# Voxx_Dott.net
KiCad netlist of a schematic drawn in EasyEDA
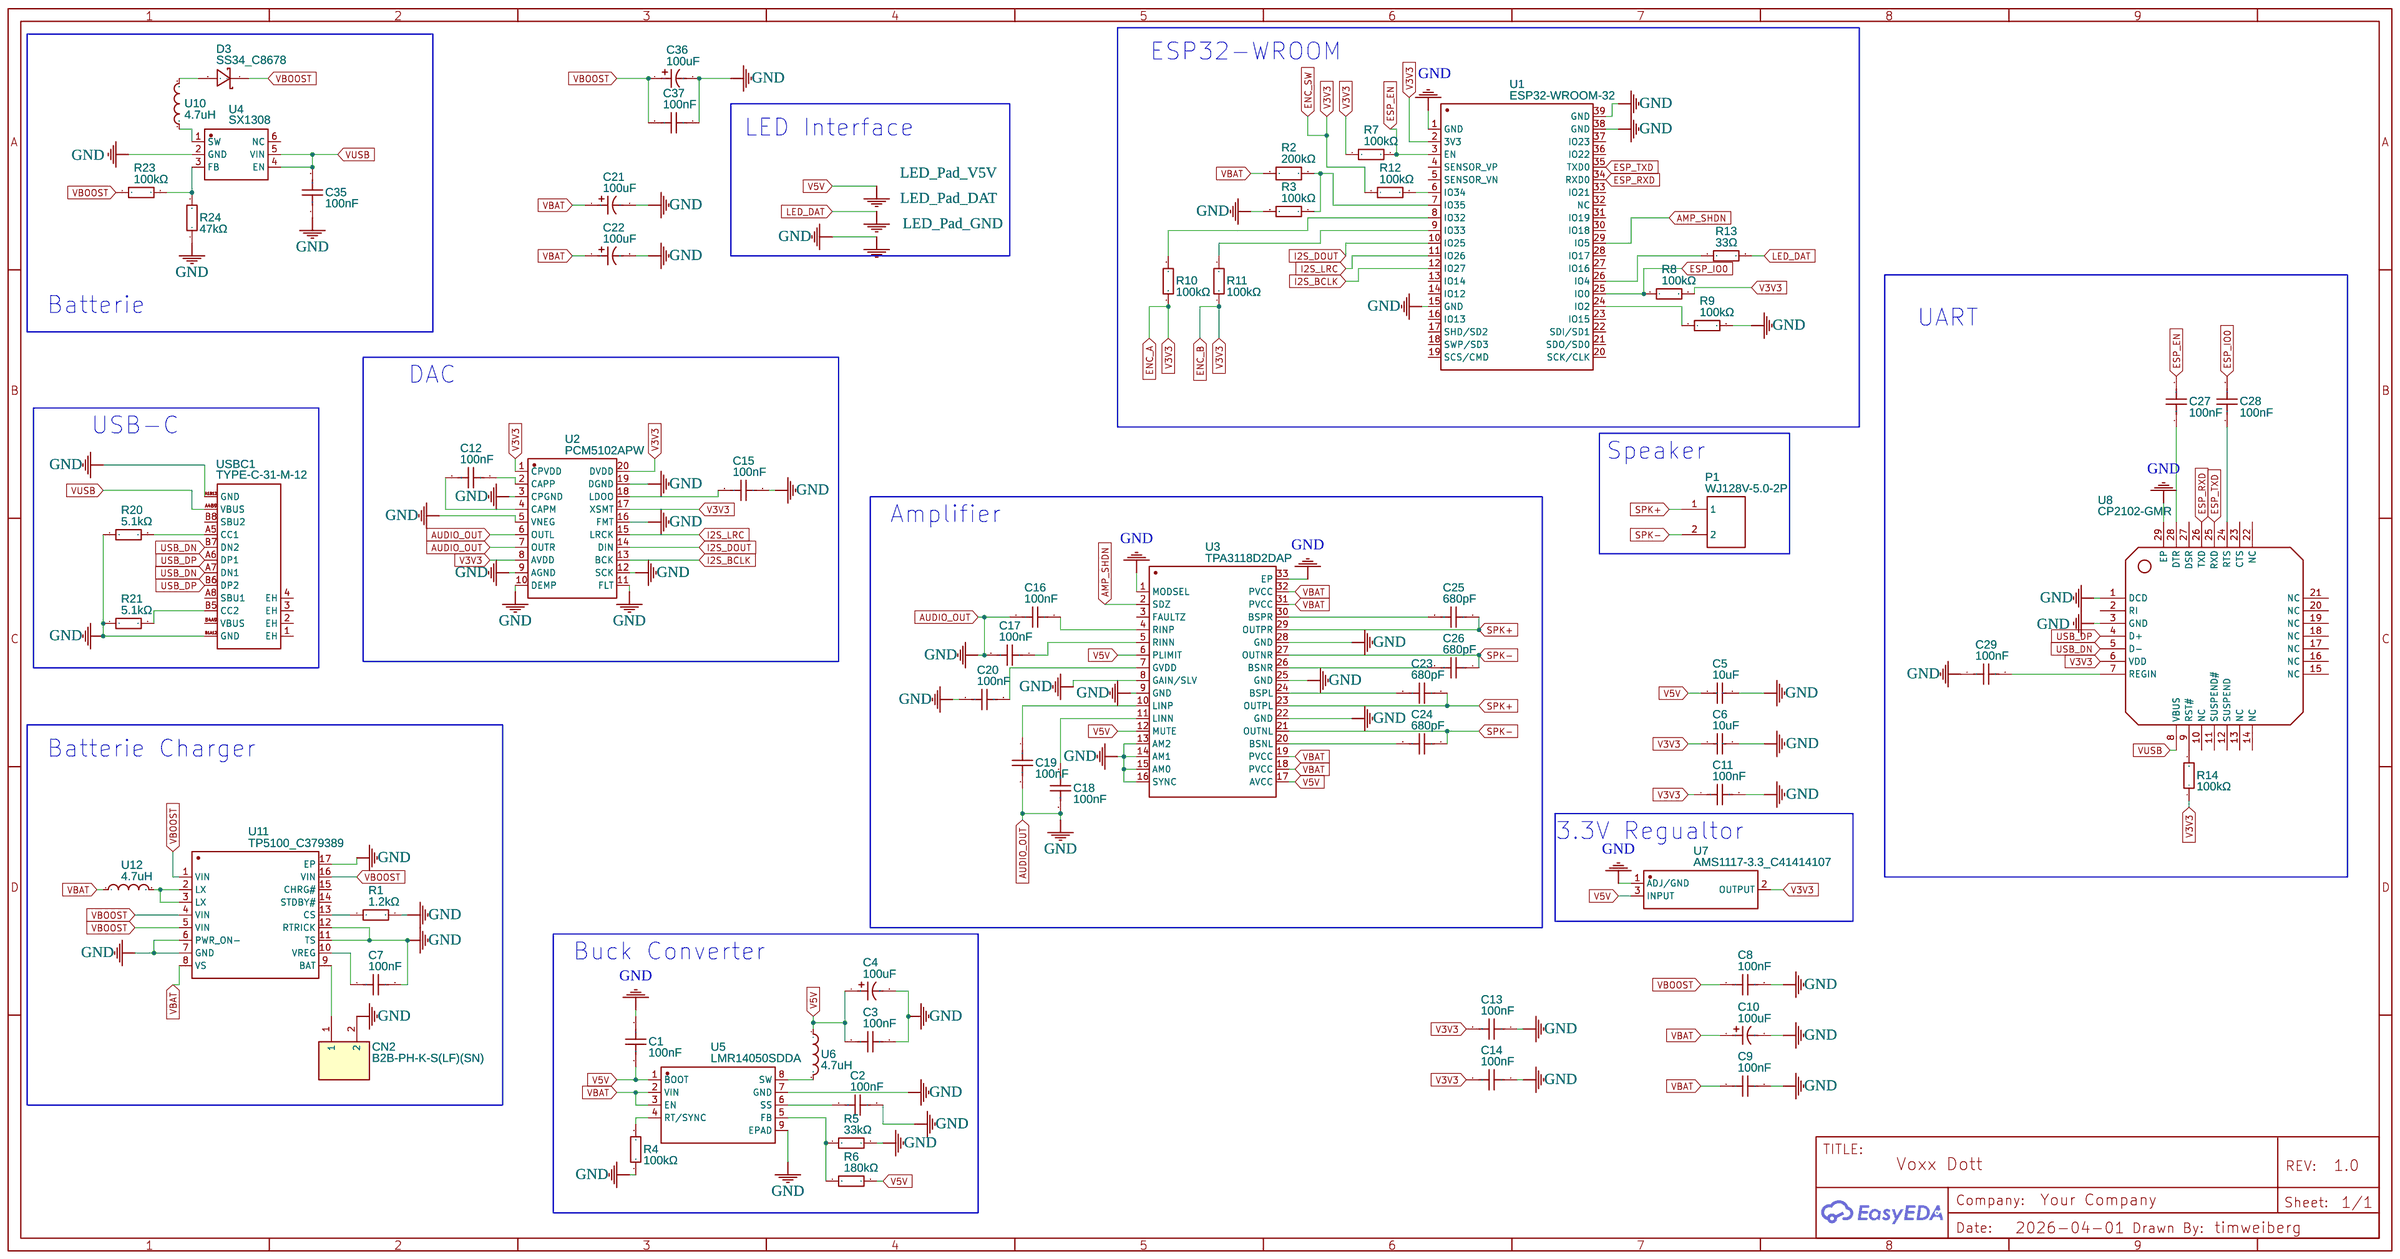
[diagram p0: schematic sheet]

(export (version "E")
  (design (tool "Eeschema 10.0.6"))
  (components
    (comp (ref "C1")
      (value "100nF")
      (fields
        (field (name "Manufacturer Part") "CC0402X7R50V104KN")
        (field (name "Manufacturer") "TORCH(火炬)")
      )
      (libsource (lib "") (part "CC0402X7R50V104KN_3"))
    )
    (comp (ref "C2")
      (value "100nF")
      (fields
        (field (name "Manufacturer Part") "CC0402X7R50V104KN")
        (field (name "Manufacturer") "TORCH(火炬)")
      )
      (libsource (lib "") (part "CC0402X7R50V104KN_2"))
    )
    (comp (ref "C3")
      (value "100nF")
      (fields
        (field (name "Manufacturer Part") "CC0402X7R50V104KN")
        (field (name "Manufacturer") "TORCH(火炬)")
      )
      (libsource (lib "") (part "CC0402X7R50V104KN_1"))
    )
    (comp (ref "C4")
      (value "100uF")
      (fields (field (name "Manufacturer Part") "MA16V100M6X8") (field (name "Manufacturer") "JIERR(捷而瑞)"))
      (libsource (lib "") (part "MA16V100M6X8"))
    )
    (comp (ref "C5")
      (value "10uF")
      (fields
        (field (name "Manufacturer Part") "CL21B106KPQNNNE")
        (field (name "Manufacturer") "SAMSUNG(三星)")
      )
      (libsource (lib "") (part "CL21B106KPQNNNE"))
    )
    (comp (ref "C6")
      (value "10uF")
      (fields
        (field (name "Manufacturer Part") "CL21B106KPQNNNE")
        (field (name "Manufacturer") "SAMSUNG(三星)")
      )
      (libsource (lib "") (part "CL21B106KPQNNNE"))
    )
    (comp (ref "C7")
      (value "100nF")
      (fields
        (field (name "Manufacturer Part") "CC0402X7R50V104KN")
        (field (name "Manufacturer") "TORCH(火炬)")
      )
      (libsource (lib "") (part "CC0402X7R50V104KN_2"))
    )
    (comp (ref "C8")
      (value "100nF")
      (fields
        (field (name "Manufacturer Part") "CC0402X7R50V104KN")
        (field (name "Manufacturer") "TORCH(火炬)")
      )
      (libsource (lib "") (part "CC0402X7R50V104KN_2"))
    )
    (comp (ref "C9")
      (value "100nF")
      (fields
        (field (name "Manufacturer Part") "CC0402X7R50V104KN")
        (field (name "Manufacturer") "TORCH(火炬)")
      )
      (libsource (lib "") (part "CC0402X7R50V104KN_2"))
    )
    (comp (ref "C10")
      (value "100uF")
      (fields (field (name "Manufacturer Part") "MA16V100M6X8") (field (name "Manufacturer") "JIERR(捷而瑞)"))
      (libsource (lib "") (part "MA16V100M6X8"))
    )
    (comp (ref "C11")
      (value "100nF")
      (fields
        (field (name "Manufacturer Part") "CC0402X7R50V104KN")
        (field (name "Manufacturer") "TORCH(火炬)")
      )
      (libsource (lib "") (part "CC0402X7R50V104KN_2"))
    )
    (comp (ref "C12")
      (value "100nF")
      (fields
        (field (name "Manufacturer Part") "CC0402X7R50V104KN")
        (field (name "Manufacturer") "TORCH(火炬)")
      )
      (libsource (lib "") (part "CC0402X7R50V104KN_1"))
    )
    (comp (ref "C13")
      (value "100nF")
      (fields
        (field (name "Manufacturer Part") "CC0402X7R50V104KN")
        (field (name "Manufacturer") "TORCH(火炬)")
      )
      (libsource (lib "") (part "CC0402X7R50V104KN_1"))
    )
    (comp (ref "C14")
      (value "100nF")
      (fields
        (field (name "Manufacturer Part") "CC0402X7R50V104KN")
        (field (name "Manufacturer") "TORCH(火炬)")
      )
      (libsource (lib "") (part "CC0402X7R50V104KN_1"))
    )
    (comp (ref "C15")
      (value "100nF")
      (fields
        (field (name "Manufacturer Part") "CC0402X7R50V104KN")
        (field (name "Manufacturer") "TORCH(火炬)")
      )
      (libsource (lib "") (part "CC0402X7R50V104KN_1"))
    )
    (comp (ref "C16")
      (value "100nF")
      (fields
        (field (name "Manufacturer Part") "CC0402X7R50V104KN")
        (field (name "Manufacturer") "TORCH(火炬)")
      )
      (libsource (lib "") (part "CC0402X7R50V104KN_1"))
    )
    (comp (ref "C17")
      (value "100nF")
      (fields
        (field (name "Manufacturer Part") "CC0402X7R50V104KN")
        (field (name "Manufacturer") "TORCH(火炬)")
      )
      (libsource (lib "") (part "CC0402X7R50V104KN_1"))
    )
    (comp (ref "C18")
      (value "100nF")
      (fields
        (field (name "Manufacturer Part") "CC0402X7R50V104KN")
        (field (name "Manufacturer") "TORCH(火炬)")
      )
      (libsource (lib "") (part "CC0402X7R50V104KN"))
    )
    (comp (ref "C19")
      (value "100nF")
      (fields
        (field (name "Manufacturer Part") "CC0402X7R50V104KN")
        (field (name "Manufacturer") "TORCH(火炬)")
      )
      (libsource (lib "") (part "CC0402X7R50V104KN"))
    )
    (comp (ref "C20")
      (value "100nF")
      (fields
        (field (name "Manufacturer Part") "CC0402X7R50V104KN")
        (field (name "Manufacturer") "TORCH(火炬)")
      )
      (libsource (lib "") (part "CC0402X7R50V104KN_2"))
    )
    (comp (ref "C21")
      (value "100uF")
      (fields (field (name "Manufacturer Part") "MA16V100M6X8") (field (name "Manufacturer") "JIERR(捷而瑞)"))
      (libsource (lib "") (part "MA16V100M6X8_1"))
    )
    (comp (ref "C22")
      (value "100uF")
      (fields (field (name "Manufacturer Part") "MA16V100M6X8") (field (name "Manufacturer") "JIERR(捷而瑞)"))
      (libsource (lib "") (part "MA16V100M6X8_1"))
    )
    (comp (ref "C23")
      (value "680pF")
      (fields
        (field (name "Manufacturer Part") "CL05C681JB5NNNC")
        (field (name "Manufacturer") "SAMSUNG(三星)")
      )
      (libsource (lib "") (part "CL05C681JB5NNNC"))
    )
    (comp (ref "C24")
      (value "680pF")
      (fields
        (field (name "Manufacturer Part") "CL05C681JB5NNNC")
        (field (name "Manufacturer") "SAMSUNG(三星)")
      )
      (libsource (lib "") (part "CL05C681JB5NNNC"))
    )
    (comp (ref "C25")
      (value "680pF")
      (fields
        (field (name "Manufacturer Part") "CL05C681JB5NNNC")
        (field (name "Manufacturer") "SAMSUNG(三星)")
      )
      (libsource (lib "") (part "CL05C681JB5NNNC"))
    )
    (comp (ref "C26")
      (value "680pF")
      (fields
        (field (name "Manufacturer Part") "CL05C681JB5NNNC")
        (field (name "Manufacturer") "SAMSUNG(三星)")
      )
      (libsource (lib "") (part "CL05C681JB5NNNC"))
    )
    (comp (ref "C27")
      (value "100nF")
      (fields
        (field (name "Manufacturer Part") "CC0402X7R50V104KN")
        (field (name "Manufacturer") "TORCH(火炬)")
      )
      (libsource (lib "") (part "CC0402X7R50V104KN_3"))
    )
    (comp (ref "C28")
      (value "100nF")
      (fields
        (field (name "Manufacturer Part") "CC0402X7R50V104KN")
        (field (name "Manufacturer") "TORCH(火炬)")
      )
      (libsource (lib "") (part "CC0402X7R50V104KN_3"))
    )
    (comp (ref "C29")
      (value "100nF")
      (fields
        (field (name "Manufacturer Part") "CC0402X7R50V104KN")
        (field (name "Manufacturer") "TORCH(火炬)")
      )
      (libsource (lib "") (part "CC0402X7R50V104KN_2"))
    )
    (comp (ref "C35")
      (value "100nF")
      (fields
        (field (name "Manufacturer Part") "CC0402X7R50V104KN")
        (field (name "Manufacturer") "TORCH(火炬)")
      )
      (libsource (lib "") (part "CC0402X7R50V104KN_3"))
    )
    (comp (ref "C36")
      (value "100uF")
      (fields (field (name "Manufacturer Part") "MA16V100M6X8") (field (name "Manufacturer") "JIERR(捷而瑞)"))
      (libsource (lib "") (part "MA16V100M6X8_1"))
    )
    (comp (ref "C37")
      (value "100nF")
      (fields
        (field (name "Manufacturer Part") "CC0402X7R50V104KN")
        (field (name "Manufacturer") "TORCH(火炬)")
      )
      (libsource (lib "") (part "CC0402X7R50V104KN_1"))
    )
    (comp (ref "CN2")
      (value "B2B-PH-K-S(LF)(SN)")
      (fields (field (name "Manufacturer") "JST"))
      (libsource (lib "") (part "B2B-PH-K-S(LF)(SN)"))
    )
    (comp (ref "D3")
      (value "SS34_C8678")
      (fields (field (name "Manufacturer Part") "SS34") (field (name "Manufacturer") "MDD(辰达半导体)"))
      (libsource (lib "") (part "SS34_C8678"))
    )
    (comp (ref "P1")
      (value "WJ128V-5.0-2P")
      (fields
        (field (name "Manufacturer Part") "WJ128V-5.0-02P-14-00A")
        (field (name "Manufacturer") "KANGNEX(康奈克斯电气)")
      )
      (libsource (lib "") (part "WJ128V-5.0-2P"))
    )
    (comp (ref "R1")
      (value "1.2kΩ")
      (fields (field (name "Manufacturer Part") "RC0402FR-071K2L") (field (name "Manufacturer") "YAGEO(国巨)"))
      (libsource (lib "") (part "RC0402FR-071K2L"))
    )
    (comp (ref "R2")
      (value "200kΩ")
      (fields (field (name "Manufacturer Part") "FRC0402F2003TS") (field (name "Manufacturer") "FOJAN(富捷)"))
      (libsource (lib "") (part "FRC0402F2003TS"))
    )
    (comp (ref "R3")
      (value "100kΩ")
      (fields (field (name "Manufacturer Part") "RC0402FR-07100KL") (field (name "Manufacturer") "YAGEO(国巨)"))
      (libsource (lib "") (part "RC0402FR-07100KL_2"))
    )
    (comp (ref "R4")
      (value "100kΩ")
      (fields (field (name "Manufacturer Part") "RC0402FR-07100KL") (field (name "Manufacturer") "YAGEO(国巨)"))
      (libsource (lib "") (part "RC0402FR-07100KL_1"))
    )
    (comp (ref "R5")
      (value "33kΩ")
      (fields (field (name "Manufacturer Part") "RC0402FR-0733KL") (field (name "Manufacturer") "YAGEO(国巨)"))
      (libsource (lib "") (part "RC0402FR-0733KL"))
    )
    (comp (ref "R6")
      (value "180kΩ")
      (fields (field (name "Manufacturer Part") "RC0402FR-07100KL") (field (name "Manufacturer") "YAGEO(国巨)"))
      (libsource (lib "") (part "RC0402FR-07100KL"))
    )
    (comp (ref "R7")
      (value "100kΩ")
      (fields (field (name "Manufacturer Part") "RC0402FR-07100KL") (field (name "Manufacturer") "YAGEO(国巨)"))
      (libsource (lib "") (part "RC0402FR-07100KL"))
    )
    (comp (ref "R8")
      (value "100kΩ")
      (fields (field (name "Manufacturer Part") "RC0402FR-07100KL") (field (name "Manufacturer") "YAGEO(国巨)"))
      (libsource (lib "") (part "RC0402FR-07100KL"))
    )
    (comp (ref "R9")
      (value "100kΩ")
      (fields (field (name "Manufacturer Part") "RC0402FR-07100KL") (field (name "Manufacturer") "YAGEO(国巨)"))
      (libsource (lib "") (part "RC0402FR-07100KL"))
    )
    (comp (ref "R10")
      (value "100kΩ")
      (fields (field (name "Manufacturer Part") "RC0402FR-07100KL") (field (name "Manufacturer") "YAGEO(国巨)"))
      (libsource (lib "") (part "RC0402FR-07100KL_1"))
    )
    (comp (ref "R11")
      (value "100kΩ")
      (fields (field (name "Manufacturer Part") "RC0402FR-07100KL") (field (name "Manufacturer") "YAGEO(国巨)"))
      (libsource (lib "") (part "RC0402FR-07100KL_1"))
    )
    (comp (ref "R12")
      (value "100kΩ")
      (fields (field (name "Manufacturer Part") "RC0402FR-07100KL") (field (name "Manufacturer") "YAGEO(国巨)"))
      (libsource (lib "") (part "RC0402FR-07100KL"))
    )
    (comp (ref "R13")
      (value "33Ω")
      (fields (field (name "Manufacturer Part") "RC0402FR-0733RL") (field (name "Manufacturer") "YAGEO(国巨)"))
      (libsource (lib "") (part "RC0402FR-0733RL"))
    )
    (comp (ref "R14")
      (value "100kΩ")
      (fields (field (name "Manufacturer Part") "RC0402FR-07100KL") (field (name "Manufacturer") "YAGEO(国巨)"))
      (libsource (lib "") (part "RC0402FR-07100KL_1"))
    )
    (comp (ref "R20")
      (value "5.1kΩ")
      (fields (field (name "Manufacturer Part") "RC0402FR-075K1L") (field (name "Manufacturer") "YAGEO(国巨)"))
      (libsource (lib "") (part "RC0402FR-075K1L"))
    )
    (comp (ref "R21")
      (value "5.1kΩ")
      (fields (field (name "Manufacturer Part") "RC0402FR-075K1L") (field (name "Manufacturer") "YAGEO(国巨)"))
      (libsource (lib "") (part "RC0402FR-075K1L"))
    )
    (comp (ref "R23")
      (value "100kΩ")
      (fields (field (name "Manufacturer Part") "RC0402FR-07100KL") (field (name "Manufacturer") "YAGEO(国巨)"))
      (libsource (lib "") (part "RC0402FR-07100KL"))
    )
    (comp (ref "R24")
      (value "47kΩ")
      (fields (field (name "Manufacturer Part") "RC0402FR-0747KL") (field (name "Manufacturer") "YAGEO(国巨)"))
      (libsource (lib "") (part "RC0402FR-0747KL"))
    )
    (comp (ref "U1")
      (value "ESP32-WROOM-32")
      (fields
        (field (name "Manufacturer Part") "ESP32-WROOM-32-N4")
        (field (name "Manufacturer") "ESPRESSIF(乐鑫)")
      )
      (libsource (lib "") (part "ESP32-WROOM-32"))
    )
    (comp (ref "U2")
      (value "PCM5102APW")
      (fields (field (name "Manufacturer") "TI(德州仪器)"))
      (libsource (lib "") (part "PCM5102APW"))
    )
    (comp (ref "U3")
      (value "TPA3118D2DAP")
      (fields (field (name "Manufacturer") "TI(德州仪器)"))
      (libsource (lib "") (part "TPA3118D2DAP"))
    )
    (comp (ref "U4")
      (value "SX1308")
      (fields (field (name "Manufacturer") "SX(硕芯科技)"))
      (libsource (lib "") (part "SX1308"))
    )
    (comp (ref "U5")
      (value "LMR14050SDDA")
      (fields (field (name "Manufacturer") "TI(德州仪器)"))
      (libsource (lib "") (part "LMR14050SDDA"))
    )
    (comp (ref "U6")
      (value "4.7uH")
      (fields (field (name "Manufacturer Part") "APH0630T4R7M") (field (name "Manufacturer") "APV(爱普微)"))
      (libsource (lib "") (part "APH0630T4R7M_2"))
    )
    (comp (ref "U7")
      (value "AMS1117-3.3_C41414107")
      (fields (field (name "Manufacturer Part") "AMS1117-3.3") (field (name "Manufacturer") "YONGYUTAI(永裕泰)"))
      (libsource (lib "") (part "AMS1117-3.3_C41414107"))
    )
    (comp (ref "U8")
      (value "CP2102-GMR")
      (fields (field (name "Manufacturer") "SKYWORKS/SILICON LABS(芯科)"))
      (libsource (lib "") (part "CP2102-GMR"))
    )
    (comp (ref "U10")
      (value "4.7uH")
      (fields (field (name "Manufacturer Part") "APH0630T4R7M") (field (name "Manufacturer") "APV(爱普微)"))
      (libsource (lib "") (part "APH0630T4R7M_1"))
    )
    (comp (ref "U11")
      (value "TP5100_C379389")
      (fields (field (name "Manufacturer Part") "TP5100") (field (name "Manufacturer") "TOPPOWER(南京拓微)"))
      (libsource (lib "") (part "TP5100_C379389"))
    )
    (comp (ref "U12")
      (value "4.7uH")
      (fields (field (name "Manufacturer Part") "APH0630T4R7M") (field (name "Manufacturer") "APV(爱普微)"))
      (libsource (lib "") (part "APH0630T4R7M"))
    )
    (comp (ref "USBC1")
      (value "TYPE-C-31-M-12")
      (fields (field (name "Manufacturer") "韩国韩荣"))
      (libsource (lib "") (part "TYPE-C-31-M-12"))
    )
  )
  (nets
    (net (code "1") (name "AMP_SHDN") (class "Default")
      (node (ref "U1") (pin "29") (pinfunction "IO5_29") (pintype "unspecified"))
      (node (ref "U3") (pin "2") (pinfunction "SDZ_2") (pintype "unspecified"))
    )
    (net (code "2") (name "AUDIO_OUT") (class "Default")
      (node (ref "C1") (pin "2") (pinfunction "2_2") (pintype "unspecified"))
      (node (ref "C10") (pin "2") (pinfunction "2_2") (pintype "input"))
      (node (ref "C11") (pin "2") (pinfunction "2_2") (pintype "unspecified"))
      (node (ref "C13") (pin "1") (pinfunction "1_1") (pintype "unspecified"))
      (node (ref "C14") (pin "1") (pinfunction "1_1") (pintype "unspecified"))
      (node (ref "C15") (pin "1") (pinfunction "1_1") (pintype "unspecified"))
      (node (ref "C16") (pin "2") (pinfunction "2_2") (pintype "unspecified"))
      (node (ref "C17") (pin "2") (pinfunction "2_2") (pintype "unspecified"))
      (node (ref "C18") (pin "2") (pinfunction "2_2") (pintype "unspecified"))
      (node (ref "C19") (pin "2") (pinfunction "2_2") (pintype "unspecified"))
      (node (ref "C2") (pin "2") (pinfunction "2_2") (pintype "unspecified"))
      (node (ref "C20") (pin "1") (pinfunction "1_1") (pintype "unspecified"))
      (node (ref "C21") (pin "2") (pinfunction "2_2") (pintype "input"))
      (node (ref "C22") (pin "2") (pinfunction "2_2") (pintype "input"))
      (node (ref "C29") (pin "1") (pinfunction "1_1") (pintype "unspecified"))
      (node (ref "C3") (pin "1") (pinfunction "1_1") (pintype "unspecified"))
      (node (ref "C35") (pin "1") (pinfunction "1_1") (pintype "unspecified"))
      (node (ref "C36") (pin "2") (pinfunction "2_2") (pintype "input"))
      (node (ref "C37") (pin "1") (pinfunction "1_1") (pintype "unspecified"))
      (node (ref "C4") (pin "2") (pinfunction "2_2") (pintype "input"))
      (node (ref "C5") (pin "2") (pinfunction "2_2") (pintype "input"))
      (node (ref "C6") (pin "2") (pinfunction "2_2") (pintype "input"))
      (node (ref "C7") (pin "2") (pinfunction "2_2") (pintype "unspecified"))
      (node (ref "C8") (pin "2") (pinfunction "2_2") (pintype "unspecified"))
      (node (ref "C9") (pin "2") (pinfunction "2_2") (pintype "unspecified"))
      (node (ref "CN2") (pin "2") (pinfunction "2_2") (pintype "input"))
      (node (ref "R1") (pin "2") (pinfunction "2_2") (pintype "input"))
      (node (ref "R20") (pin "1") (pinfunction "1_1") (pintype "input"))
      (node (ref "R21") (pin "1") (pinfunction "1_1") (pintype "input"))
      (node (ref "R24") (pin "1") (pinfunction "1_1") (pintype "input"))
      (node (ref "R3") (pin "2") (pinfunction "2_2") (pintype "input"))
      (node (ref "R4") (pin "1") (pinfunction "1_1") (pintype "input"))
      (node (ref "R5") (pin "2") (pinfunction "2_2") (pintype "input"))
      (node (ref "R9") (pin "2") (pinfunction "2_2") (pintype "input"))
      (node (ref "U1") (pin "1") (pinfunction "GND_1") (pintype "unspecified"))
      (node (ref "U1") (pin "15") (pinfunction "GND_15") (pintype "unspecified"))
      (node (ref "U1") (pin "38") (pinfunction "GND_38") (pintype "unspecified"))
      (node (ref "U1") (pin "39") (pinfunction "GND_39") (pintype "unspecified"))
      (node (ref "U11") (pin "11") (pinfunction "TS_11") (pintype "unspecified"))
      (node (ref "U11") (pin "12") (pinfunction "RTRICK_12") (pintype "unspecified"))
      (node (ref "U11") (pin "17") (pinfunction "EP_17") (pintype "unspecified"))
      (node (ref "U11") (pin "6") (pinfunction "PWR_ON-_6") (pintype "unspecified"))
      (node (ref "U11") (pin "7") (pinfunction "GND_7") (pintype "unspecified"))
      (node (ref "U2") (pin "10") (pinfunction "DEMP_10") (pintype "unspecified"))
      (node (ref "U2") (pin "11") (pinfunction "FLT_11") (pintype "unspecified"))
      (node (ref "U2") (pin "12") (pinfunction "SCK_12") (pintype "unspecified"))
      (node (ref "U2") (pin "16") (pinfunction "FMT_16") (pintype "unspecified"))
      (node (ref "U2") (pin "19") (pinfunction "DGND_19") (pintype "unspecified"))
      (node (ref "U2") (pin "3") (pinfunction "CPGND_3") (pintype "unspecified"))
      (node (ref "U2") (pin "5") (pinfunction "VNEG_5") (pintype "unspecified"))
      (node (ref "U2") (pin "6") (pinfunction "OUTL_6") (pintype "unspecified"))
      (node (ref "U2") (pin "7") (pinfunction "OUTR_7") (pintype "unspecified"))
      (node (ref "U2") (pin "9") (pinfunction "AGND_9") (pintype "unspecified"))
      (node (ref "U3") (pin "1") (pinfunction "MODSEL_1") (pintype "unspecified"))
      (node (ref "U3") (pin "13") (pinfunction "AM2_13") (pintype "unspecified"))
      (node (ref "U3") (pin "14") (pinfunction "AM1_14") (pintype "unspecified"))
      (node (ref "U3") (pin "15") (pinfunction "AM0_15") (pintype "unspecified"))
      (node (ref "U3") (pin "16") (pinfunction "SYNC_16") (pintype "unspecified"))
      (node (ref "U3") (pin "22") (pinfunction "GND_22") (pintype "unspecified"))
      (node (ref "U3") (pin "25") (pinfunction "GND_25") (pintype "unspecified"))
      (node (ref "U3") (pin "28") (pinfunction "GND_28") (pintype "unspecified"))
      (node (ref "U3") (pin "33") (pinfunction "EP_33") (pintype "unspecified"))
      (node (ref "U3") (pin "8") (pinfunction "GAIN/SLV_8") (pintype "unspecified"))
      (node (ref "U3") (pin "9") (pinfunction "GND_9") (pintype "unspecified"))
      (node (ref "U4") (pin "2") (pinfunction "GND_2") (pintype "unspecified"))
      (node (ref "U5") (pin "7") (pinfunction "GND_7") (pintype "unspecified"))
      (node (ref "U5") (pin "9") (pinfunction "EPAD_9") (pintype "unspecified"))
      (node (ref "U7") (pin "1") (pinfunction "ADJ/GND_1") (pintype "unspecified"))
      (node (ref "U8") (pin "1") (pinfunction "DCD_1") (pintype "unspecified"))
      (node (ref "U8") (pin "29") (pinfunction "EP_29") (pintype "unspecified"))
      (node (ref "U8") (pin "3") (pinfunction "GND_3") (pintype "unspecified"))
      (node (ref "USBC1") (pin "A1B12") (pinfunction "GND_A1B12") (pintype "unspecified"))
      (node (ref "USBC1") (pin "B1A12") (pinfunction "GND_B1A12") (pintype "unspecified"))
    )
    (net (code "3") (name "ENC_A") (class "Default")
      (node (ref "C11") (pin "1") (pinfunction "1_1") (pintype "unspecified"))
      (node (ref "C13") (pin "2") (pinfunction "2_2") (pintype "unspecified"))
      (node (ref "C14") (pin "2") (pinfunction "2_2") (pintype "unspecified"))
      (node (ref "C6") (pin "1") (pinfunction "1_1") (pintype "input"))
      (node (ref "R10") (pin "1") (pinfunction "1_1") (pintype "input"))
      (node (ref "R11") (pin "1") (pinfunction "1_1") (pintype "input"))
      (node (ref "R12") (pin "1") (pinfunction "1_1") (pintype "input"))
      (node (ref "R14") (pin "1") (pinfunction "1_1") (pintype "input"))
      (node (ref "R7") (pin "1") (pinfunction "1_1") (pintype "input"))
      (node (ref "R8") (pin "2") (pinfunction "2_2") (pintype "input"))
      (node (ref "U1") (pin "2") (pinfunction "3V3_2") (pintype "unspecified"))
      (node (ref "U2") (pin "1") (pinfunction "CPVDD_1") (pintype "unspecified"))
      (node (ref "U2") (pin "17") (pinfunction "XSMT_17") (pintype "unspecified"))
      (node (ref "U2") (pin "20") (pinfunction "DVDD_20") (pintype "unspecified"))
      (node (ref "U2") (pin "8") (pinfunction "AVDD_8") (pintype "unspecified"))
      (node (ref "U7") (pin "2") (pinfunction "OUTPUT_2") (pintype "unspecified"))
      (node (ref "U8") (pin "6") (pinfunction "VDD_6") (pintype "unspecified"))
    )
    (net (code "4") (name "ESP_EN") (class "Default")
      (node (ref "C27") (pin "2") (pinfunction "2_2") (pintype "unspecified"))
      (node (ref "R7") (pin "2") (pinfunction "2_2") (pintype "input"))
      (node (ref "U1") (pin "3") (pinfunction "EN_3") (pintype "unspecified"))
    )
    (net (code "5") (name "ESP_IO0") (class "Default")
      (node (ref "C28") (pin "2") (pinfunction "2_2") (pintype "unspecified"))
      (node (ref "R8") (pin "1") (pinfunction "1_1") (pintype "input"))
      (node (ref "U1") (pin "25") (pinfunction "IO0_25") (pintype "unspecified"))
    )
    (net (code "6") (name "ESP_RXD") (class "Default")
      (node (ref "U1") (pin "34") (pinfunction "RXD0_34") (pintype "unspecified"))
      (node (ref "U8") (pin "26") (pinfunction "TXD_26") (pintype "unspecified"))
    )
    (net (code "7") (name "ESP_TXD") (class "Default")
      (node (ref "U1") (pin "35") (pinfunction "TXD0_35") (pintype "unspecified"))
      (node (ref "U8") (pin "25") (pinfunction "RXD_25") (pintype "unspecified"))
    )
    (net (code "8") (name "I2S_BCLK") (class "Default")
      (node (ref "U1") (pin "12") (pinfunction "IO27_12") (pintype "unspecified"))
      (node (ref "U2") (pin "13") (pinfunction "BCK_13") (pintype "unspecified"))
    )
    (net (code "9") (name "I2S_DOUT") (class "Default")
      (node (ref "U1") (pin "10") (pinfunction "IO25_10") (pintype "unspecified"))
      (node (ref "U2") (pin "14") (pinfunction "DIN_14") (pintype "unspecified"))
    )
    (net (code "10") (name "I2S_LRC") (class "Default")
      (node (ref "U1") (pin "11") (pinfunction "IO26_11") (pintype "unspecified"))
      (node (ref "U2") (pin "15") (pinfunction "LRCK_15") (pintype "unspecified"))
    )
    (net (code "11") (name "LED_DAT") (class "Default")
      (node (ref "R13") (pin "2") (pinfunction "2_2") (pintype "input"))
    )
    (net (code "12") (name "Net-(D3-A)") (class "Default")
      (node (ref "D3") (pin "2") (pinfunction "A_2") (pintype "unspecified"))
      (node (ref "U10") (pin "2") (pinfunction "2_2") (pintype "unspecified"))
    )
    (net (code "13") (name "Net-(U1-IO2)") (class "Default")
      (node (ref "R9") (pin "1") (pinfunction "1_1") (pintype "input"))
      (node (ref "U1") (pin "24") (pinfunction "IO2_24") (pintype "unspecified"))
    )
    (net (code "14") (name "Net-(U1-IO4)") (class "Default")
      (node (ref "R13") (pin "1") (pinfunction "1_1") (pintype "input"))
      (node (ref "U1") (pin "26") (pinfunction "IO4_26") (pintype "unspecified"))
    )
    (net (code "15") (name "Net-(U1-IO32)") (class "Default")
      (node (ref "R10") (pin "2") (pinfunction "2_2") (pintype "input"))
      (node (ref "U1") (pin "8") (pinfunction "IO32_8") (pintype "unspecified"))
    )
    (net (code "16") (name "Net-(U1-IO33)") (class "Default")
      (node (ref "R11") (pin "2") (pinfunction "2_2") (pintype "input"))
      (node (ref "U1") (pin "9") (pinfunction "IO33_9") (pintype "unspecified"))
    )
    (net (code "17") (name "Net-(U1-IO34)") (class "Default")
      (node (ref "R12") (pin "2") (pinfunction "2_2") (pintype "input"))
      (node (ref "U1") (pin "6") (pinfunction "IO34_6") (pintype "unspecified"))
    )
    (net (code "18") (name "Net-(U1-IO35)") (class "Default")
      (node (ref "R2") (pin "2") (pinfunction "2_2") (pintype "unspecified"))
      (node (ref "R3") (pin "1") (pinfunction "1_1") (pintype "input"))
      (node (ref "U1") (pin "7") (pinfunction "IO35_7") (pintype "unspecified"))
    )
    (net (code "19") (name "Net-(U2-CAPM)") (class "Default")
      (node (ref "C12") (pin "2") (pinfunction "2_2") (pintype "unspecified"))
      (node (ref "U2") (pin "4") (pinfunction "CAPM_4") (pintype "unspecified"))
    )
    (net (code "20") (name "Net-(U2-CAPP)") (class "Default")
      (node (ref "C12") (pin "1") (pinfunction "1_1") (pintype "unspecified"))
      (node (ref "U2") (pin "2") (pinfunction "CAPP_2") (pintype "unspecified"))
    )
    (net (code "21") (name "Net-(U2-LDOO)") (class "Default")
      (node (ref "C15") (pin "2") (pinfunction "2_2") (pintype "unspecified"))
      (node (ref "U2") (pin "18") (pinfunction "LDOO_18") (pintype "unspecified"))
    )
    (net (code "22") (name "Net-(U3-BSNL)") (class "Default")
      (node (ref "C24") (pin "2") (pinfunction "2_2") (pintype "unspecified"))
      (node (ref "U3") (pin "20") (pinfunction "BSNL_20") (pintype "unspecified"))
    )
    (net (code "23") (name "Net-(U3-BSNR)") (class "Default")
      (node (ref "C26") (pin "2") (pinfunction "2_2") (pintype "unspecified"))
      (node (ref "U3") (pin "26") (pinfunction "BSNR_26") (pintype "unspecified"))
    )
    (net (code "24") (name "Net-(U3-BSPL)") (class "Default")
      (node (ref "C23") (pin "2") (pinfunction "2_2") (pintype "unspecified"))
      (node (ref "U3") (pin "24") (pinfunction "BSPL_24") (pintype "unspecified"))
    )
    (net (code "25") (name "Net-(U3-BSPR)") (class "Default")
      (node (ref "C25") (pin "2") (pinfunction "2_2") (pintype "unspecified"))
      (node (ref "U3") (pin "30") (pinfunction "BSPR_30") (pintype "unspecified"))
    )
    (net (code "26") (name "Net-(U3-GVDD)") (class "Default")
      (node (ref "C20") (pin "2") (pinfunction "2_2") (pintype "unspecified"))
      (node (ref "U3") (pin "7") (pinfunction "GVDD_7") (pintype "unspecified"))
    )
    (net (code "27") (name "Net-(U3-LINN)") (class "Default")
      (node (ref "C18") (pin "1") (pinfunction "1_1") (pintype "unspecified"))
      (node (ref "U3") (pin "11") (pinfunction "LINN_11") (pintype "unspecified"))
    )
    (net (code "28") (name "Net-(U3-LINP)") (class "Default")
      (node (ref "C19") (pin "1") (pinfunction "1_1") (pintype "unspecified"))
      (node (ref "U3") (pin "10") (pinfunction "LINP_10") (pintype "unspecified"))
    )
    (net (code "29") (name "Net-(U3-RINN)") (class "Default")
      (node (ref "C17") (pin "1") (pinfunction "1_1") (pintype "unspecified"))
      (node (ref "U3") (pin "5") (pinfunction "RINN_5") (pintype "unspecified"))
    )
    (net (code "30") (name "Net-(U3-RINP)") (class "Default")
      (node (ref "C16") (pin "1") (pinfunction "1_1") (pintype "unspecified"))
      (node (ref "U3") (pin "4") (pinfunction "RINP_4") (pintype "unspecified"))
    )
    (net (code "31") (name "Net-(U4-FB)") (class "Default")
      (node (ref "R23") (pin "2") (pinfunction "2_2") (pintype "input"))
      (node (ref "R24") (pin "2") (pinfunction "2_2") (pintype "input"))
      (node (ref "U4") (pin "3") (pinfunction "FB_3") (pintype "unspecified"))
    )
    (net (code "32") (name "Net-(U4-SW)") (class "Default")
      (node (ref "U10") (pin "1") (pinfunction "1_1") (pintype "unspecified"))
      (node (ref "U4") (pin "1") (pinfunction "SW_1") (pintype "unspecified"))
    )
    (net (code "33") (name "Net-(U5-FB)") (class "Default")
      (node (ref "R5") (pin "1") (pinfunction "1_1") (pintype "input"))
      (node (ref "R6") (pin "1") (pinfunction "1_1") (pintype "input"))
      (node (ref "U5") (pin "5") (pinfunction "FB_5") (pintype "unspecified"))
    )
    (net (code "34") (name "Net-(U5-RT{slash}SYNC)") (class "Default")
      (node (ref "R4") (pin "2") (pinfunction "2_2") (pintype "input"))
      (node (ref "U5") (pin "4") (pinfunction "RT/SYNC_4") (pintype "unspecified"))
    )
    (net (code "35") (name "Net-(U5-SS)") (class "Default")
      (node (ref "C2") (pin "1") (pinfunction "1_1") (pintype "unspecified"))
      (node (ref "U5") (pin "6") (pinfunction "SS_6") (pintype "unspecified"))
    )
    (net (code "36") (name "Net-(U5-SW)") (class "Default")
      (node (ref "U5") (pin "8") (pinfunction "SW_8") (pintype "unspecified"))
      (node (ref "U6") (pin "2") (pinfunction "2_2") (pintype "unspecified"))
    )
    (net (code "37") (name "Net-(U8-DTR)") (class "Default")
      (node (ref "C27") (pin "1") (pinfunction "1_1") (pintype "unspecified"))
      (node (ref "U8") (pin "28") (pinfunction "DTR_28") (pintype "unspecified"))
    )
    (net (code "38") (name "Net-(U8-REGIN)") (class "Default")
      (node (ref "C29") (pin "2") (pinfunction "2_2") (pintype "unspecified"))
      (node (ref "U8") (pin "7") (pinfunction "REGIN_7") (pintype "unspecified"))
    )
    (net (code "39") (name "Net-(U8-RST#)") (class "Default")
      (node (ref "R14") (pin "2") (pinfunction "2_2") (pintype "input"))
      (node (ref "U8") (pin "9") (pinfunction "RST#_9") (pintype "unspecified"))
    )
    (net (code "40") (name "Net-(U8-RTS)") (class "Default")
      (node (ref "C28") (pin "1") (pinfunction "1_1") (pintype "unspecified"))
      (node (ref "U8") (pin "24") (pinfunction "RTS_24") (pintype "unspecified"))
    )
    (net (code "41") (name "Net-(U11-BAT)") (class "Default")
      (node (ref "CN2") (pin "1") (pinfunction "1_1") (pintype "input"))
      (node (ref "U11") (pin "9") (pinfunction "BAT_9") (pintype "unspecified"))
    )
    (net (code "42") (name "Net-(U11-CS)") (class "Default")
      (node (ref "R1") (pin "1") (pinfunction "1_1") (pintype "input"))
      (node (ref "U11") (pin "13") (pinfunction "CS_13") (pintype "unspecified"))
    )
    (net (code "43") (name "Net-(U11-LX-Pad2)") (class "Default")
      (node (ref "U11") (pin "2") (pinfunction "LX_2") (pintype "unspecified"))
      (node (ref "U11") (pin "3") (pinfunction "LX_3") (pintype "unspecified"))
      (node (ref "U12") (pin "2") (pinfunction "2_2") (pintype "unspecified"))
    )
    (net (code "44") (name "Net-(U11-VREG)") (class "Default")
      (node (ref "C7") (pin "1") (pinfunction "1_1") (pintype "unspecified"))
      (node (ref "U11") (pin "10") (pinfunction "VREG_10") (pintype "unspecified"))
    )
    (net (code "45") (name "Net-(USBC1-CC1)") (class "Default")
      (node (ref "R20") (pin "2") (pinfunction "2_2") (pintype "input"))
      (node (ref "USBC1") (pin "A5") (pinfunction "CC1_A5") (pintype "unspecified"))
    )
    (net (code "46") (name "Net-(USBC1-CC2)") (class "Default")
      (node (ref "R21") (pin "2") (pinfunction "2_2") (pintype "input"))
      (node (ref "USBC1") (pin "B5") (pinfunction "CC2_B5") (pintype "unspecified"))
    )
    (net (code "47") (name "SPK+") (class "Default")
      (node (ref "C23") (pin "1") (pinfunction "1_1") (pintype "unspecified"))
      (node (ref "C25") (pin "1") (pinfunction "1_1") (pintype "unspecified"))
      (node (ref "P1") (pin "1") (pinfunction "1_1") (pintype "unspecified"))
      (node (ref "U3") (pin "23") (pinfunction "OUTPL_23") (pintype "unspecified"))
      (node (ref "U3") (pin "29") (pinfunction "OUTPR_29") (pintype "unspecified"))
    )
    (net (code "48") (name "SPK-") (class "Default")
      (node (ref "C24") (pin "1") (pinfunction "1_1") (pintype "unspecified"))
      (node (ref "C26") (pin "1") (pinfunction "1_1") (pintype "unspecified"))
      (node (ref "P1") (pin "2") (pinfunction "2_2") (pintype "unspecified"))
      (node (ref "U3") (pin "21") (pinfunction "OUTNL_21") (pintype "unspecified"))
      (node (ref "U3") (pin "27") (pinfunction "OUTNR_27") (pintype "unspecified"))
    )
    (net (code "49") (name "USB_DN") (class "Default")
      (node (ref "U8") (pin "5") (pinfunction "D-_5") (pintype "unspecified"))
      (node (ref "USBC1") (pin "A7") (pinfunction "DN1_A7") (pintype "unspecified"))
      (node (ref "USBC1") (pin "B7") (pinfunction "DN2_B7") (pintype "unspecified"))
    )
    (net (code "50") (name "USB_DP") (class "Default")
      (node (ref "U8") (pin "4") (pinfunction "D+_4") (pintype "unspecified"))
      (node (ref "USBC1") (pin "A6") (pinfunction "DP1_A6") (pintype "unspecified"))
      (node (ref "USBC1") (pin "B6") (pinfunction "DP2_B6") (pintype "unspecified"))
    )
    (net (code "51") (name "V5V") (class "Default")
      (node (ref "C1") (pin "1") (pinfunction "1_1") (pintype "unspecified"))
      (node (ref "C3") (pin "2") (pinfunction "2_2") (pintype "unspecified"))
      (node (ref "C4") (pin "1") (pinfunction "1_1") (pintype "input"))
      (node (ref "C5") (pin "1") (pinfunction "1_1") (pintype "input"))
      (node (ref "R6") (pin "2") (pinfunction "2_2") (pintype "input"))
      (node (ref "U3") (pin "12") (pinfunction "MUTE_12") (pintype "unspecified"))
      (node (ref "U3") (pin "17") (pinfunction "AVCC_17") (pintype "unspecified"))
      (node (ref "U3") (pin "6") (pinfunction "PLIMIT_6") (pintype "unspecified"))
      (node (ref "U5") (pin "1") (pinfunction "BOOT_1") (pintype "unspecified"))
      (node (ref "U6") (pin "1") (pinfunction "1_1") (pintype "unspecified"))
      (node (ref "U7") (pin "3") (pinfunction "INPUT_3") (pintype "unspecified"))
    )
    (net (code "52") (name "VBAT") (class "Default")
      (node (ref "C10") (pin "1") (pinfunction "1_1") (pintype "input"))
      (node (ref "C21") (pin "1") (pinfunction "1_1") (pintype "input"))
      (node (ref "C22") (pin "1") (pinfunction "1_1") (pintype "input"))
      (node (ref "C9") (pin "1") (pinfunction "1_1") (pintype "unspecified"))
      (node (ref "R2") (pin "1") (pinfunction "1_1") (pintype "unspecified"))
      (node (ref "U11") (pin "8") (pinfunction "VS_8") (pintype "unspecified"))
      (node (ref "U12") (pin "1") (pinfunction "1_1") (pintype "unspecified"))
      (node (ref "U3") (pin "18") (pinfunction "PVCC_18") (pintype "unspecified"))
      (node (ref "U3") (pin "19") (pinfunction "PVCC_19") (pintype "unspecified"))
      (node (ref "U3") (pin "31") (pinfunction "PVCC_31") (pintype "unspecified"))
      (node (ref "U3") (pin "32") (pinfunction "PVCC_32") (pintype "unspecified"))
      (node (ref "U5") (pin "2") (pinfunction "VIN_2") (pintype "unspecified"))
      (node (ref "U5") (pin "3") (pinfunction "EN_3") (pintype "unspecified"))
    )
    (net (code "53") (name "VBOOST") (class "Default")
      (node (ref "C36") (pin "1") (pinfunction "1_1") (pintype "input"))
      (node (ref "C37") (pin "2") (pinfunction "2_2") (pintype "unspecified"))
      (node (ref "C8") (pin "1") (pinfunction "1_1") (pintype "unspecified"))
      (node (ref "D3") (pin "1") (pinfunction "K_1") (pintype "unspecified"))
      (node (ref "R23") (pin "1") (pinfunction "1_1") (pintype "input"))
      (node (ref "U11") (pin "1") (pinfunction "VIN_1") (pintype "unspecified"))
      (node (ref "U11") (pin "16") (pinfunction "VIN_16") (pintype "unspecified"))
      (node (ref "U11") (pin "4") (pinfunction "VIN_4") (pintype "unspecified"))
      (node (ref "U11") (pin "5") (pinfunction "VIN_5") (pintype "unspecified"))
    )
    (net (code "54") (name "VUSB") (class "Default")
      (node (ref "C35") (pin "2") (pinfunction "2_2") (pintype "unspecified"))
      (node (ref "U4") (pin "4") (pinfunction "EN_4") (pintype "unspecified"))
      (node (ref "U4") (pin "5") (pinfunction "VIN_5") (pintype "unspecified"))
      (node (ref "U8") (pin "8") (pinfunction "VBUS_8") (pintype "unspecified"))
      (node (ref "USBC1") (pin "A4B9") (pinfunction "VBUS_A4B9") (pintype "unspecified"))
    )
    (net (code "55") (name "unconnected-(U1-IO12-Pad14)") (class "Default")
      (node (ref "U1") (pin "14") (pinfunction "IO12_14") (pintype "unspecified"))
    )
    (net (code "56") (name "unconnected-(U1-IO13-Pad16)") (class "Default")
      (node (ref "U1") (pin "16") (pinfunction "IO13_16") (pintype "unspecified"))
    )
    (net (code "57") (name "unconnected-(U1-IO14-Pad13)") (class "Default")
      (node (ref "U1") (pin "13") (pinfunction "IO14_13") (pintype "unspecified"))
    )
    (net (code "58") (name "unconnected-(U1-IO15-Pad23)") (class "Default")
      (node (ref "U1") (pin "23") (pinfunction "IO15_23") (pintype "unspecified"))
    )
    (net (code "59") (name "unconnected-(U1-IO16-Pad27)") (class "Default")
      (node (ref "U1") (pin "27") (pinfunction "IO16_27") (pintype "unspecified"))
    )
    (net (code "60") (name "unconnected-(U1-IO17-Pad28)") (class "Default")
      (node (ref "U1") (pin "28") (pinfunction "IO17_28") (pintype "unspecified"))
    )
    (net (code "61") (name "unconnected-(U1-IO18-Pad30)") (class "Default")
      (node (ref "U1") (pin "30") (pinfunction "IO18_30") (pintype "unspecified"))
    )
    (net (code "62") (name "unconnected-(U1-IO19-Pad31)") (class "Default")
      (node (ref "U1") (pin "31") (pinfunction "IO19_31") (pintype "unspecified"))
    )
    (net (code "63") (name "unconnected-(U1-IO21-Pad33)") (class "Default")
      (node (ref "U1") (pin "33") (pinfunction "IO21_33") (pintype "unspecified"))
    )
    (net (code "64") (name "unconnected-(U1-IO22-Pad36)") (class "Default")
      (node (ref "U1") (pin "36") (pinfunction "IO22_36") (pintype "unspecified"))
    )
    (net (code "65") (name "unconnected-(U1-IO23-Pad37)") (class "Default")
      (node (ref "U1") (pin "37") (pinfunction "IO23_37") (pintype "unspecified"))
    )
    (net (code "66") (name "unconnected-(U1-NC-Pad32)") (class "Default")
      (node (ref "U1") (pin "32") (pinfunction "NC_32") (pintype "unspecified"))
    )
    (net (code "67") (name "unconnected-(U1-SCK{slash}CLK-Pad20)") (class "Default")
      (node (ref "U1") (pin "20") (pinfunction "SCK/CLK_20") (pintype "unspecified"))
    )
    (net (code "68") (name "unconnected-(U1-SCS{slash}CMD-Pad19)") (class "Default")
      (node (ref "U1") (pin "19") (pinfunction "SCS/CMD_19") (pintype "unspecified"))
    )
    (net (code "69") (name "unconnected-(U1-SDI{slash}SD1-Pad22)") (class "Default")
      (node (ref "U1") (pin "22") (pinfunction "SDI/SD1_22") (pintype "unspecified"))
    )
    (net (code "70") (name "unconnected-(U1-SDO{slash}SD0-Pad21)") (class "Default")
      (node (ref "U1") (pin "21") (pinfunction "SDO/SD0_21") (pintype "unspecified"))
    )
    (net (code "71") (name "unconnected-(U1-SENSOR_VN-Pad5)") (class "Default")
      (node (ref "U1") (pin "5") (pinfunction "SENSOR_VN_5") (pintype "unspecified"))
    )
    (net (code "72") (name "unconnected-(U1-SENSOR_VP-Pad4)") (class "Default")
      (node (ref "U1") (pin "4") (pinfunction "SENSOR_VP_4") (pintype "unspecified"))
    )
    (net (code "73") (name "unconnected-(U1-SHD{slash}SD2-Pad17)") (class "Default")
      (node (ref "U1") (pin "17") (pinfunction "SHD/SD2_17") (pintype "unspecified"))
    )
    (net (code "74") (name "unconnected-(U1-SWP{slash}SD3-Pad18)") (class "Default")
      (node (ref "U1") (pin "18") (pinfunction "SWP/SD3_18") (pintype "unspecified"))
    )
    (net (code "75") (name "unconnected-(U3-FAULTZ-Pad3)") (class "Default")
      (node (ref "U3") (pin "3") (pinfunction "FAULTZ_3") (pintype "unspecified"))
    )
    (net (code "76") (name "unconnected-(U4-NC-Pad6)") (class "Default")
      (node (ref "U4") (pin "6") (pinfunction "NC_6") (pintype "unspecified"))
    )
    (net (code "77") (name "unconnected-(U8-CTS-Pad23)") (class "Default")
      (node (ref "U8") (pin "23") (pinfunction "CTS_23") (pintype "unspecified"))
    )
    (net (code "78") (name "unconnected-(U8-DSR-Pad27)") (class "Default")
      (node (ref "U8") (pin "27") (pinfunction "DSR_27") (pintype "unspecified"))
    )
    (net (code "79") (name "unconnected-(U8-NC-Pad10)") (class "Default")
      (node (ref "U8") (pin "10") (pinfunction "NC_10") (pintype "unspecified"))
    )
    (net (code "80") (name "unconnected-(U8-NC-Pad13)") (class "Default")
      (node (ref "U8") (pin "13") (pinfunction "NC_13") (pintype "unspecified"))
    )
    (net (code "81") (name "unconnected-(U8-NC-Pad14)") (class "Default")
      (node (ref "U8") (pin "14") (pinfunction "NC_14") (pintype "unspecified"))
    )
    (net (code "82") (name "unconnected-(U8-NC-Pad15)") (class "Default")
      (node (ref "U8") (pin "15") (pinfunction "NC_15") (pintype "unspecified"))
    )
    (net (code "83") (name "unconnected-(U8-NC-Pad16)") (class "Default")
      (node (ref "U8") (pin "16") (pinfunction "NC_16") (pintype "unspecified"))
    )
    (net (code "84") (name "unconnected-(U8-NC-Pad17)") (class "Default")
      (node (ref "U8") (pin "17") (pinfunction "NC_17") (pintype "unspecified"))
    )
    (net (code "85") (name "unconnected-(U8-NC-Pad18)") (class "Default")
      (node (ref "U8") (pin "18") (pinfunction "NC_18") (pintype "unspecified"))
    )
    (net (code "86") (name "unconnected-(U8-NC-Pad19)") (class "Default")
      (node (ref "U8") (pin "19") (pinfunction "NC_19") (pintype "unspecified"))
    )
    (net (code "87") (name "unconnected-(U8-NC-Pad20)") (class "Default")
      (node (ref "U8") (pin "20") (pinfunction "NC_20") (pintype "unspecified"))
    )
    (net (code "88") (name "unconnected-(U8-NC-Pad21)") (class "Default")
      (node (ref "U8") (pin "21") (pinfunction "NC_21") (pintype "unspecified"))
    )
    (net (code "89") (name "unconnected-(U8-NC-Pad22)") (class "Default")
      (node (ref "U8") (pin "22") (pinfunction "NC_22") (pintype "unspecified"))
    )
    (net (code "90") (name "unconnected-(U8-RI-Pad2)") (class "Default")
      (node (ref "U8") (pin "2") (pinfunction "RI_2") (pintype "unspecified"))
    )
    (net (code "91") (name "unconnected-(U8-SUSPEND#-Pad11)") (class "Default")
      (node (ref "U8") (pin "11") (pinfunction "SUSPEND#_11") (pintype "unspecified"))
    )
    (net (code "92") (name "unconnected-(U8-SUSPEND-Pad12)") (class "Default")
      (node (ref "U8") (pin "12") (pinfunction "SUSPEND_12") (pintype "unspecified"))
    )
    (net (code "93") (name "unconnected-(U11-CHRG#-Pad15)") (class "Default")
      (node (ref "U11") (pin "15") (pinfunction "CHRG#_15") (pintype "unspecified"))
    )
    (net (code "94") (name "unconnected-(U11-STDBY#-Pad14)") (class "Default")
      (node (ref "U11") (pin "14") (pinfunction "STDBY#_14") (pintype "unspecified"))
    )
    (net (code "95") (name "unconnected-(USBC1-EH-Pad1)") (class "Default")
      (node (ref "USBC1") (pin "1") (pinfunction "EH_1") (pintype "unspecified"))
    )
    (net (code "96") (name "unconnected-(USBC1-EH-Pad2)") (class "Default")
      (node (ref "USBC1") (pin "2") (pinfunction "EH_2") (pintype "unspecified"))
    )
    (net (code "97") (name "unconnected-(USBC1-EH-Pad3)") (class "Default")
      (node (ref "USBC1") (pin "3") (pinfunction "EH_3") (pintype "unspecified"))
    )
    (net (code "98") (name "unconnected-(USBC1-EH-Pad4)") (class "Default")
      (node (ref "USBC1") (pin "4") (pinfunction "EH_4") (pintype "unspecified"))
    )
    (net (code "99") (name "unconnected-(USBC1-SBU1-PadA8)") (class "Default")
      (node (ref "USBC1") (pin "A8") (pinfunction "SBU1_A8") (pintype "unspecified"))
    )
    (net (code "100") (name "unconnected-(USBC1-SBU2-PadB8)") (class "Default")
      (node (ref "USBC1") (pin "B8") (pinfunction "SBU2_B8") (pintype "unspecified"))
    )
    (net (code "101") (name "unconnected-(USBC1-VBUS-PadB4A9)") (class "Default")
      (node (ref "USBC1") (pin "B4A9") (pinfunction "VBUS_B4A9") (pintype "unspecified"))
    )
  )
)
